# GL850G-SCH.net
KiCad netlist of a schematic drawn in Altium Designer
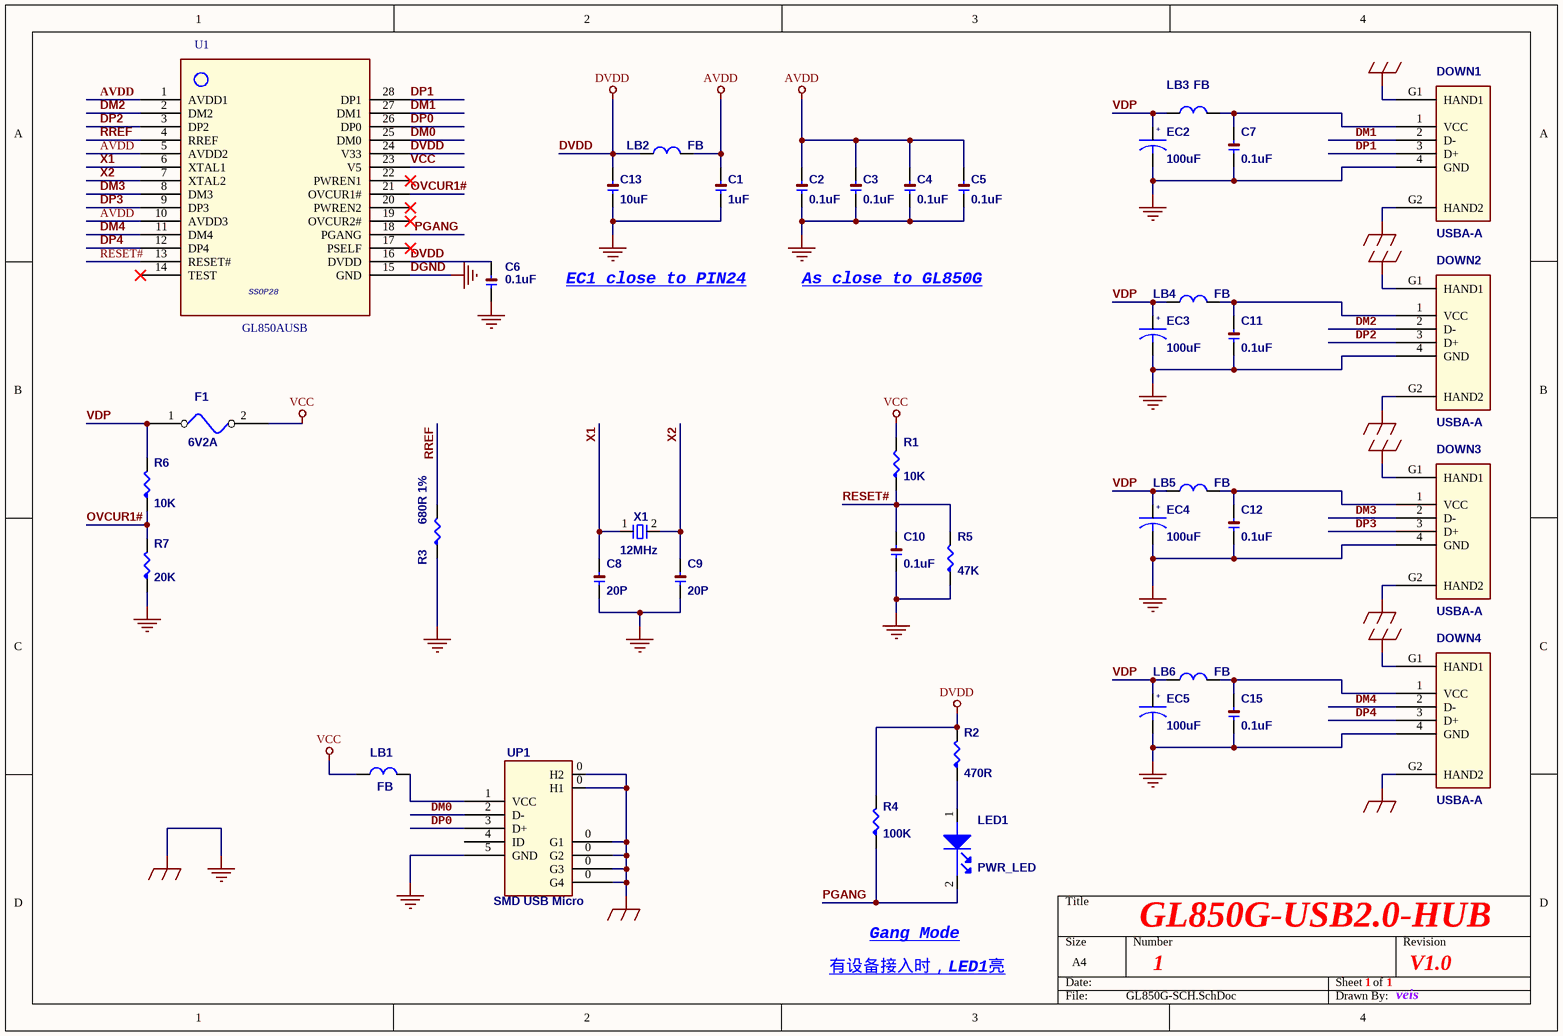
[diagram p0: GL850G-SCH.SchDoc]

(export (version "E")
  (design (tool "Eeschema 10.0.6"))
  (components
    (comp (ref "C1") (value "1uF") (footprint "C0603") (libsource (lib "*") (part "C-0603")))
    (comp (ref "C2") (value "0.1uF") (footprint "C0603") (libsource (lib "*") (part "C-0603")))
    (comp (ref "C3") (value "0.1uF") (footprint "C0603") (libsource (lib "*") (part "C-0603")))
    (comp (ref "C4") (value "0.1uF") (footprint "C0603") (libsource (lib "*") (part "C-0603")))
    (comp (ref "C5") (value "0.1uF") (footprint "C0603") (libsource (lib "*") (part "C-0603")))
    (comp (ref "C6") (value "0.1uF") (footprint "C0603") (libsource (lib "*") (part "C-0603")))
    (comp (ref "C7") (value "0.1uF") (footprint "C0603") (libsource (lib "*") (part "C-0603")))
    (comp (ref "C8") (value "20P") (footprint "C0603") (libsource (lib "*") (part "C-0603")))
    (comp (ref "C9") (value "20P") (footprint "C0603") (libsource (lib "*") (part "C-0603")))
    (comp (ref "C10") (value "0.1uF") (footprint "C0603") (libsource (lib "*") (part "C-0603")))
    (comp (ref "C11") (value "0.1uF") (footprint "C0603") (libsource (lib "*") (part "C-0603")))
    (comp (ref "C12") (value "0.1uF") (footprint "C0603") (libsource (lib "*") (part "C-0603")))
    (comp (ref "C13") (value "10uF") (footprint "C0603") (libsource (lib "*") (part "C-0603")))
    (comp (ref "C15") (value "0.1uF") (footprint "C0603") (libsource (lib "*") (part "C-0603")))
    (comp (ref "DOWN1") (value "USBA-A") (footprint "USBA-A") (libsource (lib "*") (part "USBA-A")))
    (comp (ref "DOWN2") (value "USBA-A") (footprint "USBA-A") (libsource (lib "*") (part "USBA-A")))
    (comp (ref "DOWN3") (value "USBA-A") (footprint "USBA-A") (libsource (lib "*") (part "USBA-A")))
    (comp (ref "DOWN4") (value "USBA-A") (footprint "USBA-A") (libsource (lib "*") (part "USBA-A")))
    (comp (ref "EC2") (value "100uF") (footprint "CED-6_3-2_5") (libsource (lib "*") (part "CE-100UF/16V")))
    (comp (ref "EC3") (value "100uF") (footprint "CED-6_3-2_5") (libsource (lib "*") (part "CE-100UF/16V")))
    (comp (ref "EC4") (value "100uF") (footprint "CED-6_3-2_5") (libsource (lib "*") (part "CE-100UF/16V")))
    (comp (ref "EC5") (value "100uF") (footprint "CED-6_3-2_5") (libsource (lib "*") (part "CE-100UF/16V")))
    (comp (ref "F1") (value "6V2A") (footprint "1210l") (libsource (lib "*") (part "FS-A_0")))
    (comp (ref "LB1") (value "FB") (footprint "L0805") (libsource (lib "*") (part "FB-0805")))
    (comp (ref "LB2") (value "FB") (footprint "L0805") (libsource (lib "") (part "FB-0805_1")))
    (comp (ref "LB3") (value "FB") (footprint "L0805") (libsource (lib "*") (part "FB-0805")))
    (comp (ref "LB4") (value "FB") (footprint "L0805") (libsource (lib "") (part "FB-0805_1")))
    (comp (ref "LB5") (value "FB") (footprint "L0805") (libsource (lib "") (part "FB-0805_1")))
    (comp (ref "LB6") (value "FB") (footprint "L0805") (libsource (lib "") (part "FB-0805_1")))
    (comp (ref "LED1") (value "PWR_LED") (footprint "LED_0603") (libsource (lib "*") (part "LED-3mm_0")))
    (comp (ref "R1") (value "10K") (footprint "R0603") (libsource (lib "*") (part "R-0603")))
    (comp (ref "R2") (value "470R") (footprint "R0603") (libsource (lib "*") (part "R-0603")))
    (comp (ref "R3") (value "680R 1%") (footprint "R0603") (libsource (lib "*") (part "R-0603 1%")))
    (comp (ref "R4") (value "100K") (footprint "R0603") (libsource (lib "*") (part "R-0603")))
    (comp (ref "R5") (value "47K") (footprint "R0603") (libsource (lib "*") (part "R-0603")))
    (comp (ref "R6") (value "10K") (footprint "R0603") (libsource (lib "*") (part "R-0603")))
    (comp (ref "R7") (value "20K") (footprint "R0603") (libsource (lib "*") (part "R-0603")))
    (comp (ref "U1") (value "GL850AUSB") (footprint "SSOP28") (libsource (lib "*") (part "GLI8024-48_3")))
    (comp (ref "UP1")
      (value "SMD USB Micro")
      (footprint "Micro_USB_MK5P")
      (libsource (lib "*") (part "CNS-USBminiAB-A"))
    )
    (comp (ref "X1") (value "12MHz") (footprint "XTAL-49SMA-H4.2") (libsource (lib "*") (part "XD-49US-A")))
  )
  (nets
    (net (code "1") (name "/DM0") (class "Default")
      (node (ref "U1") (pin "25") (pinfunction "DM0_25") (pintype "passive"))
      (node (ref "UP1") (pin "2") (pinfunction "D-_2") (pintype "passive"))
    )
    (net (code "2") (name "/DM1") (class "Default")
      (node (ref "DOWN1") (pin "2") (pinfunction "D-_2") (pintype "passive"))
      (node (ref "U1") (pin "27") (pinfunction "DM1_27") (pintype "passive"))
    )
    (net (code "3") (name "/DM2") (class "Default")
      (node (ref "DOWN2") (pin "2") (pinfunction "D-_2") (pintype "passive"))
      (node (ref "U1") (pin "2") (pinfunction "DM2_2") (pintype "passive"))
    )
    (net (code "4") (name "/DM3") (class "Default")
      (node (ref "DOWN3") (pin "2") (pinfunction "D-_2") (pintype "passive"))
      (node (ref "U1") (pin "8") (pinfunction "DM3_8") (pintype "passive"))
    )
    (net (code "5") (name "/DM4") (class "Default")
      (node (ref "DOWN4") (pin "2") (pinfunction "D-_2") (pintype "passive"))
      (node (ref "U1") (pin "11") (pinfunction "DM4_11") (pintype "passive"))
    )
    (net (code "6") (name "/DP0") (class "Default")
      (node (ref "U1") (pin "26") (pinfunction "DP0_26") (pintype "passive"))
      (node (ref "UP1") (pin "3") (pinfunction "D+_3") (pintype "passive"))
    )
    (net (code "7") (name "/DP1") (class "Default")
      (node (ref "DOWN1") (pin "3") (pinfunction "D+_3") (pintype "passive"))
      (node (ref "U1") (pin "28") (pinfunction "DP1_28") (pintype "passive"))
    )
    (net (code "8") (name "/DP2") (class "Default")
      (node (ref "DOWN2") (pin "3") (pinfunction "D+_3") (pintype "passive"))
      (node (ref "U1") (pin "3") (pinfunction "DP2_3") (pintype "passive"))
    )
    (net (code "9") (name "/DP3") (class "Default")
      (node (ref "DOWN3") (pin "3") (pinfunction "D+_3") (pintype "passive"))
      (node (ref "U1") (pin "9") (pinfunction "DP3_9") (pintype "passive"))
    )
    (net (code "10") (name "/DP4") (class "Default")
      (node (ref "DOWN4") (pin "3") (pinfunction "D+_3") (pintype "passive"))
      (node (ref "U1") (pin "12") (pinfunction "DP4_12") (pintype "passive"))
    )
    (net (code "11") (name "/OVCUR1#") (class "Default")
      (node (ref "R6") (pin "1") (pinfunction "1_1") (pintype "passive"))
      (node (ref "R7") (pin "2") (pinfunction "2_2") (pintype "passive"))
      (node (ref "U1") (pin "21") (pinfunction "OVCUR1#_21") (pintype "passive"))
    )
    (net (code "12") (name "/PGANG") (class "Default")
      (node (ref "LED1") (pin "2") (pinfunction "2_2") (pintype "passive"))
      (node (ref "R4") (pin "1") (pinfunction "1_1") (pintype "passive"))
      (node (ref "U1") (pin "18") (pinfunction "PGANG_18") (pintype "passive"))
    )
    (net (code "13") (name "/RESET#") (class "Default")
      (node (ref "C10") (pin "2") (pinfunction "2_2") (pintype "passive"))
      (node (ref "R1") (pin "1") (pinfunction "1_1") (pintype "passive"))
      (node (ref "R5") (pin "2") (pinfunction "2_2") (pintype "passive"))
      (node (ref "U1") (pin "13") (pinfunction "RESET#_13") (pintype "passive"))
    )
    (net (code "14") (name "/RREF") (class "Default")
      (node (ref "R3") (pin "2") (pinfunction "2_2") (pintype "passive"))
      (node (ref "U1") (pin "4") (pinfunction "RREF_4") (pintype "passive"))
    )
    (net (code "15") (name "/VDP") (class "Default")
      (node (ref "EC2") (pin "1") (pinfunction "1_1") (pintype "passive"))
      (node (ref "EC3") (pin "1") (pinfunction "1_1") (pintype "passive"))
      (node (ref "EC4") (pin "1") (pinfunction "1_1") (pintype "passive"))
      (node (ref "EC5") (pin "1") (pinfunction "1_1") (pintype "passive"))
      (node (ref "F1") (pin "1") (pinfunction "1_1") (pintype "passive"))
      (node (ref "LB3") (pin "1") (pinfunction "1_1") (pintype "passive"))
      (node (ref "LB4") (pin "2") (pinfunction "2_2") (pintype "passive"))
      (node (ref "LB5") (pin "2") (pinfunction "2_2") (pintype "passive"))
      (node (ref "LB6") (pin "2") (pinfunction "2_2") (pintype "passive"))
      (node (ref "R6") (pin "2") (pinfunction "2_2") (pintype "passive"))
    )
    (net (code "16") (name "/X1") (class "Default")
      (node (ref "C8") (pin "2") (pinfunction "2_2") (pintype "passive"))
      (node (ref "U1") (pin "6") (pinfunction "XTAL1_6") (pintype "passive"))
      (node (ref "X1") (pin "1") (pinfunction "1_1") (pintype "passive"))
    )
    (net (code "17") (name "/X2") (class "Default")
      (node (ref "C9") (pin "2") (pinfunction "2_2") (pintype "passive"))
      (node (ref "U1") (pin "7") (pinfunction "XTAL2_7") (pintype "passive"))
      (node (ref "X1") (pin "2") (pinfunction "2_2") (pintype "passive"))
    )
    (net (code "18") (name "AVDD") (class "Default")
      (node (ref "C1") (pin "2") (pinfunction "2_2") (pintype "passive"))
      (node (ref "C2") (pin "2") (pinfunction "2_2") (pintype "passive"))
      (node (ref "C3") (pin "2") (pinfunction "2_2") (pintype "passive"))
      (node (ref "C4") (pin "2") (pinfunction "2_2") (pintype "passive"))
      (node (ref "C5") (pin "2") (pinfunction "2_2") (pintype "passive"))
      (node (ref "LB2") (pin "1") (pinfunction "1_1") (pintype "passive"))
      (node (ref "U1") (pin "1") (pinfunction "AVDD1_1") (pintype "passive"))
      (node (ref "U1") (pin "10") (pinfunction "AVDD3_10") (pintype "passive"))
      (node (ref "U1") (pin "5") (pinfunction "AVDD2_5") (pintype "passive"))
    )
    (net (code "19") (name "DGND") (class "Default")
      (node (ref "C1") (pin "1") (pinfunction "1_1") (pintype "passive"))
      (node (ref "C10") (pin "1") (pinfunction "1_1") (pintype "passive"))
      (node (ref "C11") (pin "1") (pinfunction "1_1") (pintype "passive"))
      (node (ref "C12") (pin "1") (pinfunction "1_1") (pintype "passive"))
      (node (ref "C13") (pin "1") (pinfunction "1_1") (pintype "passive"))
      (node (ref "C15") (pin "1") (pinfunction "1_1") (pintype "passive"))
      (node (ref "C2") (pin "1") (pinfunction "1_1") (pintype "passive"))
      (node (ref "C3") (pin "1") (pinfunction "1_1") (pintype "passive"))
      (node (ref "C4") (pin "1") (pinfunction "1_1") (pintype "passive"))
      (node (ref "C5") (pin "1") (pinfunction "1_1") (pintype "passive"))
      (node (ref "C6") (pin "1") (pinfunction "1_1") (pintype "passive"))
      (node (ref "C7") (pin "1") (pinfunction "1_1") (pintype "passive"))
      (node (ref "C8") (pin "1") (pinfunction "1_1") (pintype "passive"))
      (node (ref "C9") (pin "1") (pinfunction "1_1") (pintype "passive"))
      (node (ref "DOWN1") (pin "4") (pinfunction "GND_4") (pintype "passive"))
      (node (ref "DOWN1") (pin "G1") (pinfunction "HAND1_G1") (pintype "passive"))
      (node (ref "DOWN1") (pin "G2") (pinfunction "HAND2_G2") (pintype "passive"))
      (node (ref "DOWN2") (pin "4") (pinfunction "GND_4") (pintype "passive"))
      (node (ref "DOWN2") (pin "G1") (pinfunction "HAND1_G1") (pintype "passive"))
      (node (ref "DOWN2") (pin "G2") (pinfunction "HAND2_G2") (pintype "passive"))
      (node (ref "DOWN3") (pin "4") (pinfunction "GND_4") (pintype "passive"))
      (node (ref "DOWN3") (pin "G1") (pinfunction "HAND1_G1") (pintype "passive"))
      (node (ref "DOWN3") (pin "G2") (pinfunction "HAND2_G2") (pintype "passive"))
      (node (ref "DOWN4") (pin "4") (pinfunction "GND_4") (pintype "passive"))
      (node (ref "DOWN4") (pin "G1") (pinfunction "HAND1_G1") (pintype "passive"))
      (node (ref "DOWN4") (pin "G2") (pinfunction "HAND2_G2") (pintype "passive"))
      (node (ref "EC2") (pin "2") (pinfunction "2_2") (pintype "passive"))
      (node (ref "EC3") (pin "2") (pinfunction "2_2") (pintype "passive"))
      (node (ref "EC4") (pin "2") (pinfunction "2_2") (pintype "passive"))
      (node (ref "EC5") (pin "2") (pinfunction "2_2") (pintype "passive"))
      (node (ref "R3") (pin "1") (pinfunction "1_1") (pintype "passive"))
      (node (ref "R5") (pin "1") (pinfunction "1_1") (pintype "passive"))
      (node (ref "R7") (pin "1") (pinfunction "1_1") (pintype "passive"))
      (node (ref "U1") (pin "15") (pinfunction "GND_15") (pintype "passive"))
      (node (ref "UP1") (pin "0") (pinfunction "G3_0") (pintype "passive"))
      (node (ref "UP1") (pin "5") (pinfunction "GND_5") (pintype "passive"))
    )
    (net (code "20") (name "DVDD") (class "Default")
      (node (ref "C13") (pin "2") (pinfunction "2_2") (pintype "passive"))
      (node (ref "C6") (pin "2") (pinfunction "2_2") (pintype "passive"))
      (node (ref "LB2") (pin "2") (pinfunction "2_2") (pintype "passive"))
      (node (ref "R2") (pin "2") (pinfunction "2_2") (pintype "passive"))
      (node (ref "R4") (pin "2") (pinfunction "2_2") (pintype "passive"))
      (node (ref "U1") (pin "16") (pinfunction "DVDD_16") (pintype "passive"))
      (node (ref "U1") (pin "24") (pinfunction "V33_24") (pintype "passive"))
    )
    (net (code "21") (name "Net-(DOWN1-VCC)") (class "Default")
      (node (ref "C7") (pin "2") (pinfunction "2_2") (pintype "passive"))
      (node (ref "DOWN1") (pin "1") (pinfunction "VCC_1") (pintype "passive"))
      (node (ref "LB3") (pin "2") (pinfunction "2_2") (pintype "passive"))
    )
    (net (code "22") (name "Net-(DOWN2-VCC)") (class "Default")
      (node (ref "C11") (pin "2") (pinfunction "2_2") (pintype "passive"))
      (node (ref "DOWN2") (pin "1") (pinfunction "VCC_1") (pintype "passive"))
      (node (ref "LB4") (pin "1") (pinfunction "1_1") (pintype "passive"))
    )
    (net (code "23") (name "Net-(DOWN3-VCC)") (class "Default")
      (node (ref "C12") (pin "2") (pinfunction "2_2") (pintype "passive"))
      (node (ref "DOWN3") (pin "1") (pinfunction "VCC_1") (pintype "passive"))
      (node (ref "LB5") (pin "1") (pinfunction "1_1") (pintype "passive"))
    )
    (net (code "24") (name "Net-(DOWN4-VCC)") (class "Default")
      (node (ref "C15") (pin "2") (pinfunction "2_2") (pintype "passive"))
      (node (ref "DOWN4") (pin "1") (pinfunction "VCC_1") (pintype "passive"))
      (node (ref "LB6") (pin "1") (pinfunction "1_1") (pintype "passive"))
    )
    (net (code "25") (name "Net-(LED1-Pad1)") (class "Default")
      (node (ref "LED1") (pin "1") (pinfunction "1_1") (pintype "passive"))
      (node (ref "R2") (pin "1") (pinfunction "1_1") (pintype "passive"))
    )
    (net (code "26") (name "Net-(UP1-VCC)") (class "Default")
      (node (ref "LB1") (pin "2") (pinfunction "2_2") (pintype "passive"))
      (node (ref "UP1") (pin "1") (pinfunction "VCC_1") (pintype "passive"))
    )
    (net (code "27") (name "VCC") (class "Default")
      (node (ref "F1") (pin "2") (pinfunction "2_2") (pintype "passive"))
      (node (ref "LB1") (pin "1") (pinfunction "1_1") (pintype "passive"))
      (node (ref "R1") (pin "2") (pinfunction "2_2") (pintype "passive"))
      (node (ref "U1") (pin "23") (pinfunction "V5_23") (pintype "passive"))
    )
    (net (code "28") (name "unconnected-(U1-OVCUR2#-Pad19)") (class "Default")
      (node (ref "U1") (pin "19") (pinfunction "OVCUR2#_19") (pintype "passive+no_connect"))
    )
    (net (code "29") (name "unconnected-(U1-PSELF-Pad17)") (class "Default")
      (node (ref "U1") (pin "17") (pinfunction "PSELF_17") (pintype "passive+no_connect"))
    )
    (net (code "30") (name "unconnected-(U1-PWREN1-Pad22)") (class "Default")
      (node (ref "U1") (pin "22") (pinfunction "PWREN1_22") (pintype "passive+no_connect"))
    )
    (net (code "31") (name "unconnected-(U1-PWREN2-Pad20)") (class "Default")
      (node (ref "U1") (pin "20") (pinfunction "PWREN2_20") (pintype "passive+no_connect"))
    )
    (net (code "32") (name "unconnected-(U1-TEST-Pad14)") (class "Default")
      (node (ref "U1") (pin "14") (pinfunction "TEST_14") (pintype "passive+no_connect"))
    )
    (net (code "33") (name "unconnected-(UP1-ID-Pad4)") (class "Default")
      (node (ref "UP1") (pin "4") (pinfunction "ID_4") (pintype "passive"))
    )
  )
)
